# Side.net
KiCad netlist of a schematic drawn in Altium Designer
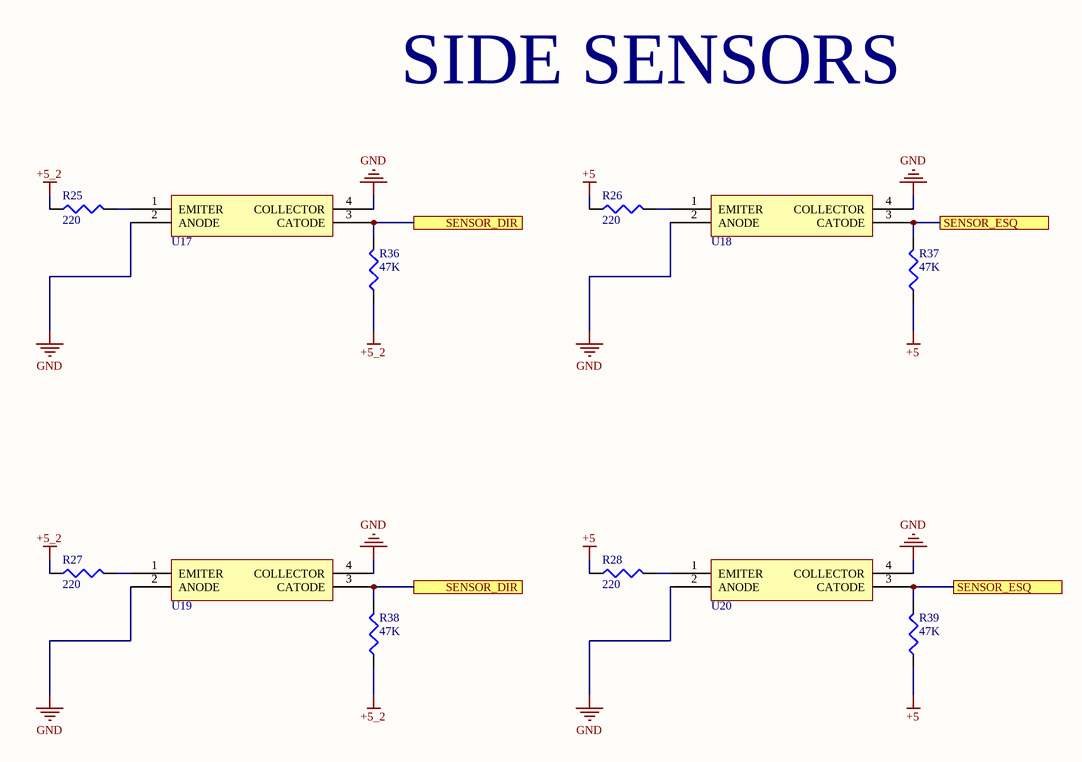
[diagram p0: Side.SchDoc]

(export (version "E")
  (design (tool "Eeschema 10.0.6"))
  (components
    (comp (ref "R25")
      (value "220")
      (footprint "6-0805_M")
      (description "RES SMD 220 OHM 1% 1/8W 0805")
      (fields
        (field (name "MANUFACTURER") "Vishay Semiconductors")
        (field (name "MANUFACTURER PART NUMBER") "CRCW0805220RFKEAC")
      )
      (libsource (lib "BiricuticoBonito") (part "Resistor 220 0805"))
    )
    (comp (ref "R26")
      (value "220")
      (footprint "6-0805_M")
      (description "RES SMD 220 OHM 1% 1/8W 0805")
      (fields
        (field (name "MANUFACTURER") "Vishay Semiconductors")
        (field (name "MANUFACTURER PART NUMBER") "CRCW0805220RFKEAC")
      )
      (libsource (lib "BiricuticoBonito") (part "Resistor 220 0805"))
    )
    (comp (ref "R27")
      (value "220")
      (footprint "6-0805_M")
      (description "RES SMD 220 OHM 1% 1/8W 0805")
      (fields
        (field (name "MANUFACTURER") "Vishay Semiconductors")
        (field (name "MANUFACTURER PART NUMBER") "CRCW0805220RFKEAC")
      )
      (libsource (lib "BiricuticoBonito") (part "Resistor 220 0805"))
    )
    (comp (ref "R28")
      (value "220")
      (footprint "6-0805_M")
      (description "RES SMD 220 OHM 1% 1/8W 0805")
      (fields
        (field (name "MANUFACTURER") "Vishay Semiconductors")
        (field (name "MANUFACTURER PART NUMBER") "CRCW0805220RFKEAC")
      )
      (libsource (lib "BiricuticoBonito") (part "Resistor 220 0805"))
    )
    (comp (ref "R36")
      (value "47K")
      (footprint "6-0805_M")
      (description "RES SMD 47K OHM 1% 1/8W 0805")
      (fields
        (field (name "MANUFACTURER") "Vishay")
        (field (name "MANUFACTURER PART NUMBER") "CRCW080547K0FKEA")
      )
      (libsource (lib "BiricuticoBonito") (part "Resistor 47K 0805"))
    )
    (comp (ref "R37")
      (value "47K")
      (footprint "6-0805_M")
      (description "RES SMD 47K OHM 1% 1/8W 0805")
      (fields
        (field (name "MANUFACTURER") "Vishay")
        (field (name "MANUFACTURER PART NUMBER") "CRCW080547K0FKEA")
      )
      (libsource (lib "BiricuticoBonito") (part "Resistor 47K 0805"))
    )
    (comp (ref "R38")
      (value "47K")
      (footprint "6-0805_M")
      (description "RES SMD 47K OHM 1% 1/8W 0805")
      (fields
        (field (name "MANUFACTURER") "Vishay")
        (field (name "MANUFACTURER PART NUMBER") "CRCW080547K0FKEA")
      )
      (libsource (lib "BiricuticoBonito") (part "Resistor 47K 0805"))
    )
    (comp (ref "R39")
      (value "47K")
      (footprint "6-0805_M")
      (description "RES SMD 47K OHM 1% 1/8W 0805")
      (fields
        (field (name "MANUFACTURER") "Vishay")
        (field (name "MANUFACTURER PART NUMBER") "CRCW080547K0FKEA")
      )
      (libsource (lib "BiricuticoBonito") (part "Resistor 47K 0805"))
    )
    (comp (ref "U17")
      (value "Optical Switches")
      (footprint "QRE1113GR")
      (description "SENSOR OPTO TRANS REFL SMD PHOTO")
      (fields
        (field (name "MANUFACTURER") "ON Semiconductor / Fairchild")
        (field (name "MANUFACTURER PART NUMBER") "QRE1113GR")
      )
      (libsource (lib "BiricuticoBonito") (part "Optical Switches"))
    )
    (comp (ref "U18")
      (value "Optical Switches")
      (footprint "QRE1113GR")
      (description "SENSOR OPTO TRANS REFL SMD PHOTO")
      (fields
        (field (name "MANUFACTURER") "ON Semiconductor / Fairchild")
        (field (name "MANUFACTURER PART NUMBER") "QRE1113GR")
      )
      (libsource (lib "BiricuticoBonito") (part "Optical Switches"))
    )
    (comp (ref "U19")
      (value "Optical Switches")
      (footprint "QRE1113GR")
      (description "SENSOR OPTO TRANS REFL SMD PHOTO")
      (fields
        (field (name "MANUFACTURER") "ON Semiconductor / Fairchild")
        (field (name "MANUFACTURER PART NUMBER") "QRE1113GR")
      )
      (libsource (lib "BiricuticoBonito") (part "Optical Switches"))
    )
    (comp (ref "U20")
      (value "Optical Switches")
      (footprint "QRE1113GR")
      (description "SENSOR OPTO TRANS REFL SMD PHOTO")
      (fields
        (field (name "MANUFACTURER") "ON Semiconductor / Fairchild")
        (field (name "MANUFACTURER PART NUMBER") "QRE1113GR")
      )
      (libsource (lib "BiricuticoBonito") (part "Optical Switches"))
    )
  )
  (nets
    (net (code "1") (name "+5") (class "Default")
      (node (ref "R26") (pin "1") (pinfunction "28_1") (pintype "passive"))
      (node (ref "R28") (pin "1") (pinfunction "28_1") (pintype "passive"))
      (node (ref "R37") (pin "1") (pinfunction "28_1") (pintype "passive"))
      (node (ref "R39") (pin "1") (pinfunction "28_1") (pintype "passive"))
    )
    (net (code "2") (name "+5_2") (class "Default")
      (node (ref "R25") (pin "1") (pinfunction "28_1") (pintype "passive"))
      (node (ref "R27") (pin "1") (pinfunction "28_1") (pintype "passive"))
      (node (ref "R36") (pin "1") (pinfunction "28_1") (pintype "passive"))
      (node (ref "R38") (pin "1") (pinfunction "28_1") (pintype "passive"))
    )
    (net (code "3") (name "/SENSOR_DIR") (class "Default")
      (node (ref "R36") (pin "2") (pinfunction "27_2") (pintype "passive"))
      (node (ref "R38") (pin "2") (pinfunction "27_2") (pintype "passive"))
      (node (ref "U17") (pin "3") (pinfunction "CATODE_3") (pintype "passive"))
      (node (ref "U19") (pin "3") (pinfunction "CATODE_3") (pintype "passive"))
    )
    (net (code "4") (name "/SENSOR_ESQ") (class "Default")
      (node (ref "R37") (pin "2") (pinfunction "27_2") (pintype "passive"))
      (node (ref "R39") (pin "2") (pinfunction "27_2") (pintype "passive"))
      (node (ref "U18") (pin "3") (pinfunction "CATODE_3") (pintype "passive"))
      (node (ref "U20") (pin "3") (pinfunction "CATODE_3") (pintype "passive"))
    )
    (net (code "5") (name "GND") (class "Default")
      (node (ref "U17") (pin "2") (pinfunction "ANODE_2") (pintype "passive"))
      (node (ref "U17") (pin "4") (pinfunction "COLLECTOR_4") (pintype "passive"))
      (node (ref "U18") (pin "2") (pinfunction "ANODE_2") (pintype "passive"))
      (node (ref "U18") (pin "4") (pinfunction "COLLECTOR_4") (pintype "passive"))
      (node (ref "U19") (pin "2") (pinfunction "ANODE_2") (pintype "passive"))
      (node (ref "U19") (pin "4") (pinfunction "COLLECTOR_4") (pintype "passive"))
      (node (ref "U20") (pin "2") (pinfunction "ANODE_2") (pintype "passive"))
      (node (ref "U20") (pin "4") (pinfunction "COLLECTOR_4") (pintype "passive"))
    )
    (net (code "6") (name "Net-(R25-27)") (class "Default")
      (node (ref "R25") (pin "2") (pinfunction "27_2") (pintype "passive"))
      (node (ref "U17") (pin "1") (pinfunction "EMITER_1") (pintype "passive"))
    )
    (net (code "7") (name "Net-(R26-27)") (class "Default")
      (node (ref "R26") (pin "2") (pinfunction "27_2") (pintype "passive"))
      (node (ref "U18") (pin "1") (pinfunction "EMITER_1") (pintype "passive"))
    )
    (net (code "8") (name "Net-(R27-27)") (class "Default")
      (node (ref "R27") (pin "2") (pinfunction "27_2") (pintype "passive"))
      (node (ref "U19") (pin "1") (pinfunction "EMITER_1") (pintype "passive"))
    )
    (net (code "9") (name "Net-(R28-27)") (class "Default")
      (node (ref "R28") (pin "2") (pinfunction "27_2") (pintype "passive"))
      (node (ref "U20") (pin "1") (pinfunction "EMITER_1") (pintype "passive"))
    )
  )
)
